# sch1.net
KiCad netlist of a schematic drawn in Altium Designer
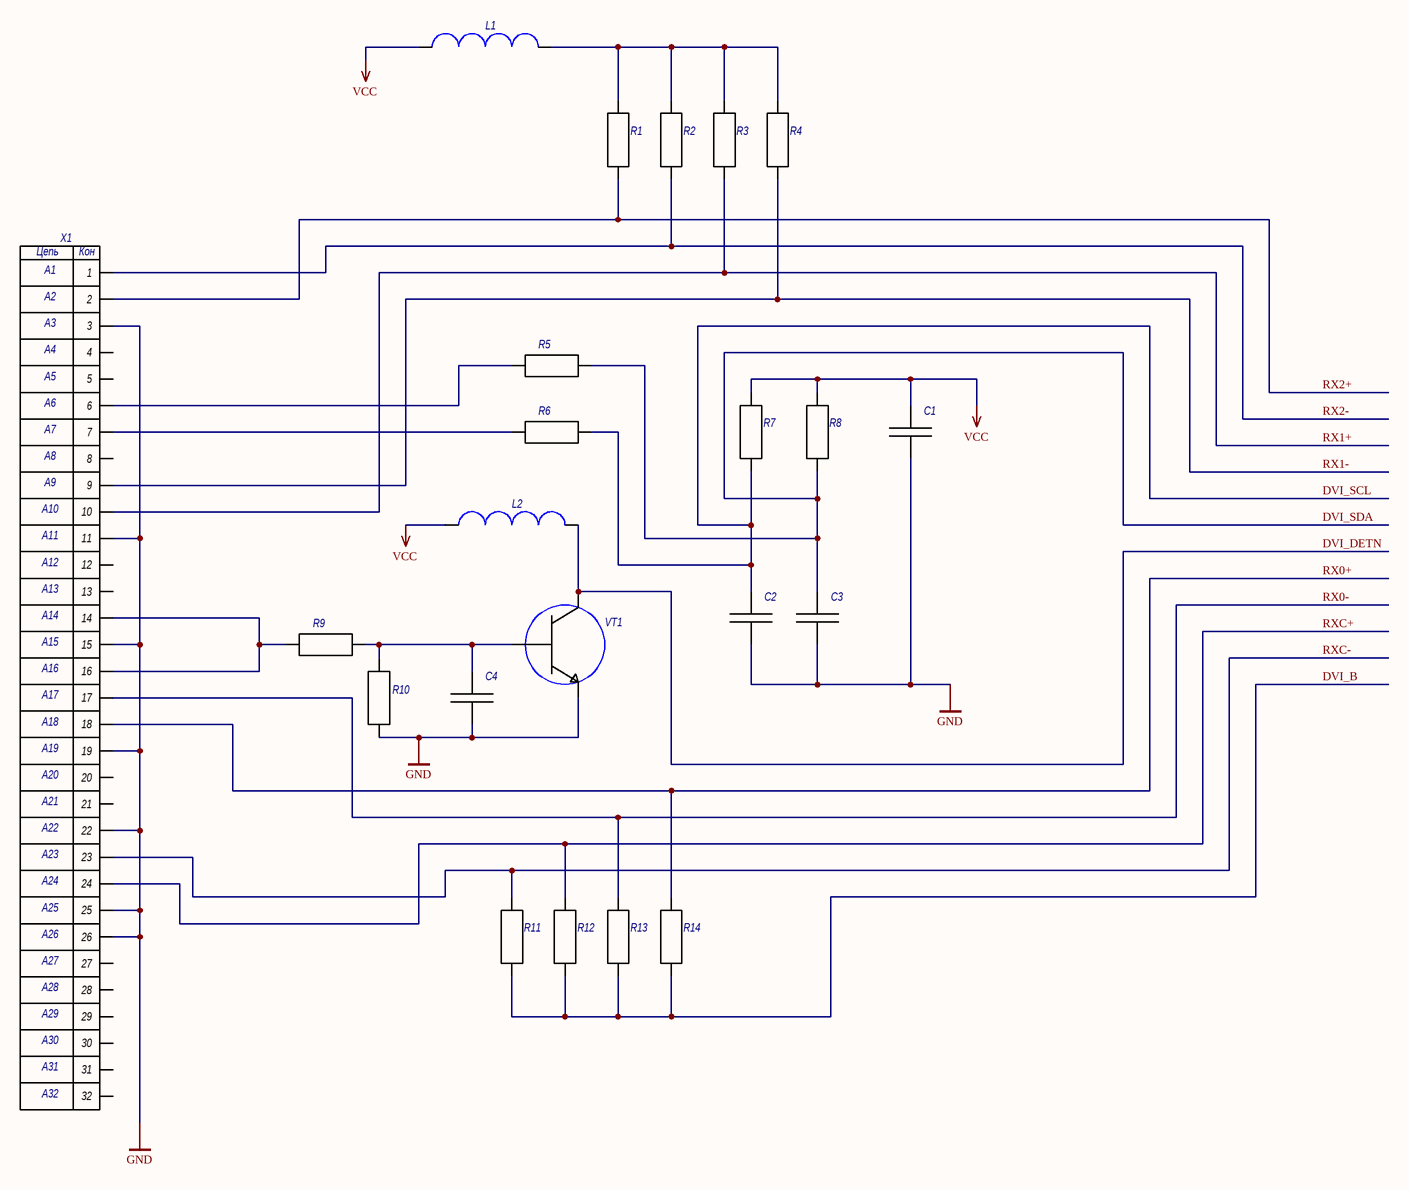
[diagram p0: sch1.SchDoc]

(export (version "E")
  (design (tool "Eeschema 10.0.6"))
  (components
    (comp (ref "C1") (value "*") (footprint "Capacitor 0805") (libsource (lib "k7shared") (part "Capacitor")))
    (comp (ref "C2") (value "*") (footprint "Capacitor 0805") (libsource (lib "k7shared") (part "Capacitor")))
    (comp (ref "C3") (value "*") (footprint "Capacitor 0805") (libsource (lib "k7shared") (part "Capacitor")))
    (comp (ref "C4") (value "*") (footprint "Capacitor 0805") (libsource (lib "k7shared") (part "Capacitor")))
    (comp (ref "L1") (value "*") (footprint "Inductor 2520") (libsource (lib "k7shared") (part "Inductor")))
    (comp (ref "L2") (value "*") (footprint "Inductor 2520") (libsource (lib "k7shared") (part "Inductor")))
    (comp (ref "R1") (value "*") (footprint "Resistor 1206") (libsource (lib "k7shared") (part "Resistor")))
    (comp (ref "R2") (value "*") (footprint "Resistor 1206") (libsource (lib "k7shared") (part "Resistor")))
    (comp (ref "R3") (value "*") (footprint "Resistor 1206") (libsource (lib "k7shared") (part "Resistor")))
    (comp (ref "R4") (value "*") (footprint "Resistor 1206") (libsource (lib "k7shared") (part "Resistor")))
    (comp (ref "R5") (value "*") (footprint "Resistor 1206") (libsource (lib "k7shared") (part "Resistor")))
    (comp (ref "R6") (value "*") (footprint "Resistor 1206") (libsource (lib "k7shared") (part "Resistor")))
    (comp (ref "R7") (value "*") (footprint "Resistor 1206") (libsource (lib "k7shared") (part "Resistor")))
    (comp (ref "R8") (value "*") (footprint "Resistor 1206") (libsource (lib "k7shared") (part "Resistor")))
    (comp (ref "R9") (value "*") (footprint "Resistor 1206") (libsource (lib "k7shared") (part "Resistor")))
    (comp (ref "R10") (value "*") (footprint "Resistor 1206") (libsource (lib "k7shared") (part "Resistor")))
    (comp (ref "R11") (value "*") (footprint "Resistor 1206") (libsource (lib "k7shared") (part "Resistor")))
    (comp (ref "R12") (value "*") (footprint "Resistor 1206") (libsource (lib "k7shared") (part "Resistor")))
    (comp (ref "R13") (value "*") (footprint "Resistor 1206") (libsource (lib "k7shared") (part "Resistor")))
    (comp (ref "R14") (value "*") (footprint "Resistor 1206") (libsource (lib "k7shared") (part "Resistor")))
    (comp (ref "VT1")
      (value "*")
      (footprint "Transistor 1")
      (libsource (lib "k7shared") (part "Transistor 1"))
    )
    (comp (ref "X1")
      (value "*")
      (footprint "DVI Connector")
      (libsource (lib "k7sch1") (part "DVI Connector"))
    )
  )
  (nets
    (net (code "1") (name "/DVI_B") (class "Default")
      (node (ref "R11") (pin "1") (pinfunction "1_1") (pintype "passive"))
      (node (ref "R12") (pin "1") (pinfunction "1_1") (pintype "passive"))
      (node (ref "R13") (pin "1") (pinfunction "1_1") (pintype "passive"))
      (node (ref "R14") (pin "1") (pinfunction "1_1") (pintype "passive"))
    )
    (net (code "2") (name "/DVI_DETN") (class "Default")
      (node (ref "L2") (pin "2") (pinfunction "2_2") (pintype "passive"))
      (node (ref "VT1") (pin "2") (pinfunction "EMITTER_2") (pintype "passive"))
    )
    (net (code "3") (name "/DVI_SCL") (class "Default")
      (node (ref "C2") (pin "2") (pinfunction "2_2") (pintype "passive"))
      (node (ref "R6") (pin "2") (pinfunction "2_2") (pintype "passive"))
      (node (ref "R7") (pin "1") (pinfunction "1_1") (pintype "passive"))
    )
    (net (code "4") (name "/DVI_SDA") (class "Default")
      (node (ref "C3") (pin "2") (pinfunction "2_2") (pintype "passive"))
      (node (ref "R5") (pin "2") (pinfunction "2_2") (pintype "passive"))
      (node (ref "R8") (pin "1") (pinfunction "1_1") (pintype "passive"))
    )
    (net (code "5") (name "/RX0+") (class "Default")
      (node (ref "R14") (pin "2") (pinfunction "2_2") (pintype "passive"))
      (node (ref "X1") (pin "18") (pinfunction "18_18") (pintype "passive"))
    )
    (net (code "6") (name "/RX0-") (class "Default")
      (node (ref "R13") (pin "2") (pinfunction "2_2") (pintype "passive"))
      (node (ref "X1") (pin "17") (pinfunction "17_17") (pintype "passive"))
    )
    (net (code "7") (name "/RX1+") (class "Default")
      (node (ref "R3") (pin "1") (pinfunction "1_1") (pintype "passive"))
      (node (ref "X1") (pin "10") (pinfunction "10_10") (pintype "passive"))
    )
    (net (code "8") (name "/RX1-") (class "Default")
      (node (ref "R4") (pin "1") (pinfunction "1_1") (pintype "passive"))
      (node (ref "X1") (pin "9") (pinfunction "9_9") (pintype "passive"))
    )
    (net (code "9") (name "/RX2+") (class "Default")
      (node (ref "R1") (pin "1") (pinfunction "1_1") (pintype "passive"))
      (node (ref "X1") (pin "2") (pinfunction "2_2") (pintype "passive"))
    )
    (net (code "10") (name "/RX2-") (class "Default")
      (node (ref "R2") (pin "1") (pinfunction "1_1") (pintype "passive"))
      (node (ref "X1") (pin "1") (pinfunction "1_1") (pintype "passive"))
    )
    (net (code "11") (name "/RXC+") (class "Default")
      (node (ref "R12") (pin "2") (pinfunction "2_2") (pintype "passive"))
      (node (ref "X1") (pin "24") (pinfunction "24_24") (pintype "passive"))
    )
    (net (code "12") (name "/RXC-") (class "Default")
      (node (ref "R11") (pin "2") (pinfunction "2_2") (pintype "passive"))
      (node (ref "X1") (pin "23") (pinfunction "23_23") (pintype "passive"))
    )
    (net (code "13") (name "GND") (class "Default")
      (node (ref "C1") (pin "1") (pinfunction "1_1") (pintype "passive"))
      (node (ref "C2") (pin "1") (pinfunction "1_1") (pintype "passive"))
      (node (ref "C3") (pin "1") (pinfunction "1_1") (pintype "passive"))
      (node (ref "C4") (pin "1") (pinfunction "1_1") (pintype "passive"))
      (node (ref "R10") (pin "1") (pinfunction "1_1") (pintype "passive"))
      (node (ref "VT1") (pin "1") (pinfunction "KOLLECTOR_1") (pintype "passive"))
      (node (ref "X1") (pin "11") (pinfunction "11_11") (pintype "passive"))
      (node (ref "X1") (pin "15") (pinfunction "15_15") (pintype "passive"))
      (node (ref "X1") (pin "19") (pinfunction "19_19") (pintype "passive"))
      (node (ref "X1") (pin "22") (pinfunction "22_22") (pintype "passive"))
      (node (ref "X1") (pin "25") (pinfunction "25_25") (pintype "passive"))
      (node (ref "X1") (pin "26") (pinfunction "26_26") (pintype "passive"))
      (node (ref "X1") (pin "3") (pinfunction "3_3") (pintype "passive"))
    )
    (net (code "14") (name "Net-(L1-Pad2)") (class "Default")
      (node (ref "L1") (pin "2") (pinfunction "2_2") (pintype "passive"))
      (node (ref "R1") (pin "2") (pinfunction "2_2") (pintype "passive"))
      (node (ref "R2") (pin "2") (pinfunction "2_2") (pintype "passive"))
      (node (ref "R3") (pin "2") (pinfunction "2_2") (pintype "passive"))
      (node (ref "R4") (pin "2") (pinfunction "2_2") (pintype "passive"))
    )
    (net (code "15") (name "Net-(R5-Pad1)") (class "Default")
      (node (ref "R5") (pin "1") (pinfunction "1_1") (pintype "passive"))
      (node (ref "X1") (pin "6") (pinfunction "6_6") (pintype "passive"))
    )
    (net (code "16") (name "Net-(R6-Pad1)") (class "Default")
      (node (ref "R6") (pin "1") (pinfunction "1_1") (pintype "passive"))
      (node (ref "X1") (pin "7") (pinfunction "7_7") (pintype "passive"))
    )
    (net (code "17") (name "Net-(R9-Pad1)") (class "Default")
      (node (ref "R9") (pin "1") (pinfunction "1_1") (pintype "passive"))
      (node (ref "X1") (pin "14") (pinfunction "14_14") (pintype "passive"))
      (node (ref "X1") (pin "16") (pinfunction "16_16") (pintype "passive"))
    )
    (net (code "18") (name "Net-(VT1-BAZA)") (class "Default")
      (node (ref "C4") (pin "2") (pinfunction "2_2") (pintype "passive"))
      (node (ref "R10") (pin "2") (pinfunction "2_2") (pintype "passive"))
      (node (ref "R9") (pin "2") (pinfunction "2_2") (pintype "passive"))
      (node (ref "VT1") (pin "3") (pinfunction "BAZA_3") (pintype "passive"))
    )
    (net (code "19") (name "VCC") (class "Default")
      (node (ref "C1") (pin "2") (pinfunction "2_2") (pintype "passive"))
      (node (ref "L1") (pin "1") (pinfunction "1_1") (pintype "passive"))
      (node (ref "L2") (pin "1") (pinfunction "1_1") (pintype "passive"))
      (node (ref "R7") (pin "2") (pinfunction "2_2") (pintype "passive"))
      (node (ref "R8") (pin "2") (pinfunction "2_2") (pintype "passive"))
    )
    (net (code "20") (name "unconnected-(X1-Pad4)") (class "Default")
      (node (ref "X1") (pin "4") (pinfunction "4_4") (pintype "passive"))
    )
    (net (code "21") (name "unconnected-(X1-Pad5)") (class "Default")
      (node (ref "X1") (pin "5") (pinfunction "5_5") (pintype "passive"))
    )
    (net (code "22") (name "unconnected-(X1-Pad8)") (class "Default")
      (node (ref "X1") (pin "8") (pinfunction "8_8") (pintype "passive"))
    )
    (net (code "23") (name "unconnected-(X1-Pad12)") (class "Default")
      (node (ref "X1") (pin "12") (pinfunction "12_12") (pintype "passive"))
    )
    (net (code "24") (name "unconnected-(X1-Pad13)") (class "Default")
      (node (ref "X1") (pin "13") (pinfunction "13_13") (pintype "passive"))
    )
    (net (code "25") (name "unconnected-(X1-Pad20)") (class "Default")
      (node (ref "X1") (pin "20") (pinfunction "20_20") (pintype "passive"))
    )
    (net (code "26") (name "unconnected-(X1-Pad21)") (class "Default")
      (node (ref "X1") (pin "21") (pinfunction "21_21") (pintype "passive"))
    )
    (net (code "27") (name "unconnected-(X1-Pad27)") (class "Default")
      (node (ref "X1") (pin "27") (pinfunction "27_27") (pintype "passive"))
    )
    (net (code "28") (name "unconnected-(X1-Pad28)") (class "Default")
      (node (ref "X1") (pin "28") (pinfunction "28_28") (pintype "passive"))
    )
    (net (code "29") (name "unconnected-(X1-Pad29)") (class "Default")
      (node (ref "X1") (pin "29") (pinfunction "29_29") (pintype "passive"))
    )
    (net (code "30") (name "unconnected-(X1-Pad30)") (class "Default")
      (node (ref "X1") (pin "30") (pinfunction "30_30") (pintype "passive"))
    )
    (net (code "31") (name "unconnected-(X1-Pad31)") (class "Default")
      (node (ref "X1") (pin "31") (pinfunction "31_31") (pintype "passive"))
    )
    (net (code "32") (name "unconnected-(X1-Pad32)") (class "Default")
      (node (ref "X1") (pin "32") (pinfunction "32_32") (pintype "passive"))
    )
  )
)
